# DualEncoderBoard-revd.net
KiCad netlist of a schematic drawn in EAGLE
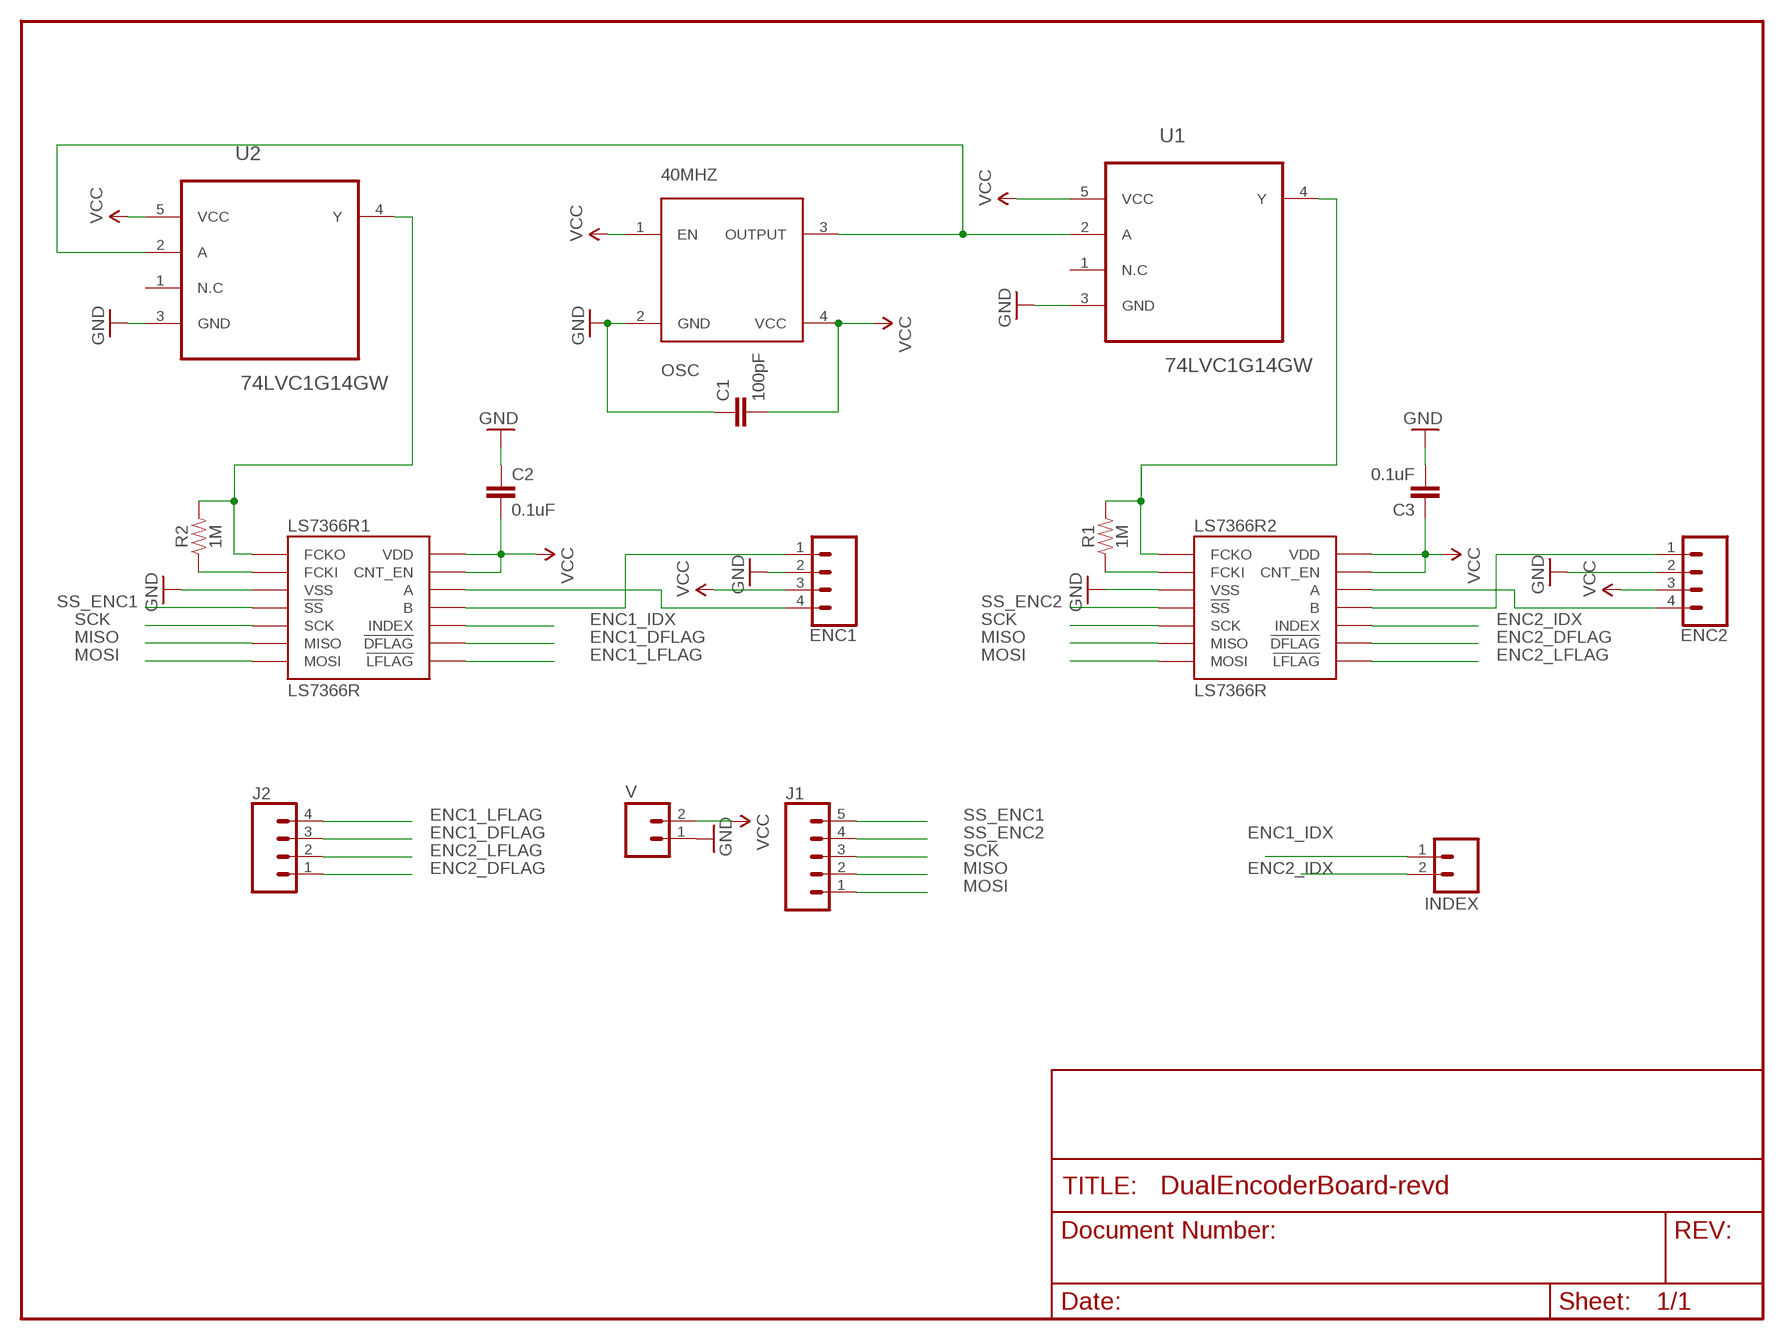
[diagram p0: schematic, sheet 1]

(export (version "E")
  (design (tool "Eeschema 10.0.6"))
  (components
    (comp (ref "40MHZ")
      (value "OSC")
      (footprint "eagle-import:CB3OSCILLATOR")
      (libsource (lib "eagle-import") (part "OSC"))
    )
    (comp (ref "C1")
      (value "100pF")
      (footprint "eagle-import:0603")
      (libsource (lib "eagle-import") (part "100PF-0603-50V-5%"))
    )
    (comp (ref "C2")
      (value "0.1uF")
      (footprint "eagle-import:0603")
      (libsource (lib "eagle-import") (part "0.1UF-0603-25V-5%"))
    )
    (comp (ref "C3")
      (value "0.1uF")
      (footprint "eagle-import:0603")
      (libsource (lib "eagle-import") (part "0.1UF-0603-25V-5%"))
    )
    (comp (ref "ENC1")
      (value "CONN_04")
      (footprint "eagle-import:1X04")
      (libsource (lib "eagle-import") (part "CONN_04"))
    )
    (comp (ref "ENC2")
      (value "CONN_04")
      (footprint "eagle-import:1X04")
      (libsource (lib "eagle-import") (part "CONN_04"))
    )
    (comp (ref "INDEX")
      (value "M02PTH")
      (footprint "eagle-import:1X02")
      (libsource (lib "eagle-import") (part "M02PTH"))
    )
    (comp (ref "J1")
      (value "CONN_05")
      (footprint "eagle-import:1X05")
      (libsource (lib "eagle-import") (part "CONN_05"))
    )
    (comp (ref "J2")
      (value "CONN_04")
      (footprint "eagle-import:1X04")
      (libsource (lib "eagle-import") (part "CONN_04"))
    )
    (comp (ref "LS7366R1")
      (value "LS7366R")
      (footprint "eagle-import:SOIC14")
      (fields (field (name "MF") "LSI"))
      (libsource (lib "eagle-import") (part "LS7366R"))
    )
    (comp (ref "LS7366R2")
      (value "LS7366R")
      (footprint "eagle-import:SOIC14")
      (fields (field (name "MF") "LSI"))
      (libsource (lib "eagle-import") (part "LS7366R"))
    )
    (comp (ref "R1")
      (value "1M")
      (footprint "eagle-import:0603")
      (libsource (lib "eagle-import") (part "1MOHM-0603-1/4W-5%"))
    )
    (comp (ref "R2")
      (value "1M")
      (footprint "eagle-import:0603")
      (libsource (lib "eagle-import") (part "1MOHM-0603-1/4W-5%"))
    )
    (comp (ref "U1")
      (value "74LVC1G14GW")
      (footprint "eagle-import:SOT65P210X110-5N")
      (fields (field (name "MF") "NXP Semiconductors"))
      (libsource (lib "eagle-import") (part "74LVC1G14GW"))
    )
    (comp (ref "U2")
      (value "74LVC1G14GW")
      (footprint "eagle-import:SOT65P210X110-5N")
      (fields (field (name "MF") "NXP Semiconductors"))
      (libsource (lib "eagle-import") (part "74LVC1G14GW"))
    )
    (comp (ref "V")
      (value "M02-JST-2MM-SMT")
      (footprint "eagle-import:JST-2-SMD")
      (libsource (lib "eagle-import") (part "M02-JST-2MM-SMT"))
    )
  )
  (nets
    (net (code "1") (name "/ENC1_DFLAG") (class "Default")
      (node (ref "J2") (pin "3") (pinfunction "3_3") (pintype "passive"))
      (node (ref "LS7366R1") (pin "9") (pinfunction "~{DFLAG}_9") (pintype "bidirectional"))
    )
    (net (code "2") (name "/ENC1_IDX") (class "Default")
      (node (ref "INDEX") (pin "1") (pinfunction "1_1") (pintype "passive"))
      (node (ref "LS7366R1") (pin "10") (pinfunction "INDEX_10") (pintype "bidirectional"))
    )
    (net (code "3") (name "/ENC1_LFLAG") (class "Default")
      (node (ref "J2") (pin "4") (pinfunction "4_4") (pintype "passive"))
      (node (ref "LS7366R1") (pin "8") (pinfunction "~{LFLAG}_8") (pintype "bidirectional"))
    )
    (net (code "4") (name "/ENC2_DFLAG") (class "Default")
      (node (ref "J2") (pin "1") (pinfunction "1_1") (pintype "passive"))
      (node (ref "LS7366R2") (pin "9") (pinfunction "~{DFLAG}_9") (pintype "bidirectional"))
    )
    (net (code "5") (name "/ENC2_IDX") (class "Default")
      (node (ref "INDEX") (pin "2") (pinfunction "2_2") (pintype "passive"))
      (node (ref "LS7366R2") (pin "10") (pinfunction "INDEX_10") (pintype "bidirectional"))
    )
    (net (code "6") (name "/ENC2_LFLAG") (class "Default")
      (node (ref "J2") (pin "2") (pinfunction "2_2") (pintype "passive"))
      (node (ref "LS7366R2") (pin "8") (pinfunction "~{LFLAG}_8") (pintype "bidirectional"))
    )
    (net (code "7") (name "/MISO") (class "Default")
      (node (ref "J1") (pin "2") (pinfunction "2_2") (pintype "passive"))
      (node (ref "LS7366R1") (pin "6") (pinfunction "MISO_6") (pintype "bidirectional"))
      (node (ref "LS7366R2") (pin "6") (pinfunction "MISO_6") (pintype "bidirectional"))
    )
    (net (code "8") (name "/MOSI") (class "Default")
      (node (ref "J1") (pin "1") (pinfunction "1_1") (pintype "passive"))
      (node (ref "LS7366R1") (pin "7") (pinfunction "MOSI_7") (pintype "bidirectional"))
      (node (ref "LS7366R2") (pin "7") (pinfunction "MOSI_7") (pintype "bidirectional"))
    )
    (net (code "9") (name "/SCK") (class "Default")
      (node (ref "J1") (pin "3") (pinfunction "3_3") (pintype "passive"))
      (node (ref "LS7366R1") (pin "5") (pinfunction "SCK_5") (pintype "bidirectional"))
      (node (ref "LS7366R2") (pin "5") (pinfunction "SCK_5") (pintype "bidirectional"))
    )
    (net (code "10") (name "/SS_ENC1") (class "Default")
      (node (ref "J1") (pin "5") (pinfunction "5_5") (pintype "passive"))
      (node (ref "LS7366R1") (pin "4") (pinfunction "~{SS}_4") (pintype "bidirectional"))
    )
    (net (code "11") (name "/SS_ENC2") (class "Default")
      (node (ref "J1") (pin "4") (pinfunction "4_4") (pintype "passive"))
      (node (ref "LS7366R2") (pin "4") (pinfunction "~{SS}_4") (pintype "bidirectional"))
    )
    (net (code "12") (name "GND") (class "Default")
      (node (ref "40MHZ") (pin "2") (pinfunction "GND_2") (pintype "input"))
      (node (ref "C1") (pin "1") (pinfunction "1_1") (pintype "passive"))
      (node (ref "C2") (pin "1") (pinfunction "1_1") (pintype "passive"))
      (node (ref "C3") (pin "2") (pinfunction "2_2") (pintype "passive"))
      (node (ref "ENC1") (pin "2") (pinfunction "2_2") (pintype "passive"))
      (node (ref "ENC2") (pin "2") (pinfunction "2_2") (pintype "passive"))
      (node (ref "LS7366R1") (pin "3") (pinfunction "VSS_3") (pintype "bidirectional"))
      (node (ref "LS7366R2") (pin "3") (pinfunction "VSS_3") (pintype "bidirectional"))
      (node (ref "U1") (pin "3") (pinfunction "GND_3") (pintype "passive"))
      (node (ref "U2") (pin "3") (pinfunction "GND_3") (pintype "passive"))
      (node (ref "V") (pin "1") (pinfunction "1_1") (pintype "passive"))
    )
    (net (code "13") (name "Net-(40MHZ-OUTPUT)") (class "Default")
      (node (ref "40MHZ") (pin "3") (pinfunction "OUTPUT_3") (pintype "output"))
      (node (ref "U1") (pin "2") (pinfunction "A_2") (pintype "input"))
      (node (ref "U2") (pin "2") (pinfunction "A_2") (pintype "input"))
    )
    (net (code "14") (name "Net-(LS7366R1-A)") (class "Default")
      (node (ref "ENC1") (pin "4") (pinfunction "4_4") (pintype "passive"))
      (node (ref "LS7366R1") (pin "12") (pinfunction "A_12") (pintype "bidirectional"))
    )
    (net (code "15") (name "Net-(LS7366R1-B)") (class "Default")
      (node (ref "ENC1") (pin "1") (pinfunction "1_1") (pintype "passive"))
      (node (ref "LS7366R1") (pin "11") (pinfunction "B_11") (pintype "bidirectional"))
    )
    (net (code "16") (name "Net-(LS7366R1-FCKI)") (class "Default")
      (node (ref "LS7366R1") (pin "2") (pinfunction "FCKI_2") (pintype "bidirectional"))
      (node (ref "R2") (pin "1") (pinfunction "1_1") (pintype "passive"))
    )
    (net (code "17") (name "Net-(LS7366R1-FCKO)") (class "Default")
      (node (ref "LS7366R1") (pin "1") (pinfunction "FCKO_1") (pintype "bidirectional"))
      (node (ref "R2") (pin "2") (pinfunction "2_2") (pintype "passive"))
      (node (ref "U2") (pin "4") (pinfunction "Y_4") (pintype "output"))
    )
    (net (code "18") (name "Net-(LS7366R2-A)") (class "Default")
      (node (ref "ENC2") (pin "4") (pinfunction "4_4") (pintype "passive"))
      (node (ref "LS7366R2") (pin "12") (pinfunction "A_12") (pintype "bidirectional"))
    )
    (net (code "19") (name "Net-(LS7366R2-B)") (class "Default")
      (node (ref "ENC2") (pin "1") (pinfunction "1_1") (pintype "passive"))
      (node (ref "LS7366R2") (pin "11") (pinfunction "B_11") (pintype "bidirectional"))
    )
    (net (code "20") (name "Net-(LS7366R2-FCKI)") (class "Default")
      (node (ref "LS7366R2") (pin "2") (pinfunction "FCKI_2") (pintype "bidirectional"))
      (node (ref "R1") (pin "1") (pinfunction "1_1") (pintype "passive"))
    )
    (net (code "21") (name "Net-(LS7366R2-FCKO)") (class "Default")
      (node (ref "LS7366R2") (pin "1") (pinfunction "FCKO_1") (pintype "bidirectional"))
      (node (ref "R1") (pin "2") (pinfunction "2_2") (pintype "passive"))
      (node (ref "U1") (pin "4") (pinfunction "Y_4") (pintype "output"))
    )
    (net (code "22") (name "VCC") (class "Default")
      (node (ref "40MHZ") (pin "1") (pinfunction "EN_1") (pintype "input"))
      (node (ref "40MHZ") (pin "4") (pinfunction "VCC_4") (pintype "input"))
      (node (ref "C1") (pin "2") (pinfunction "2_2") (pintype "passive"))
      (node (ref "C2") (pin "2") (pinfunction "2_2") (pintype "passive"))
      (node (ref "C3") (pin "1") (pinfunction "1_1") (pintype "passive"))
      (node (ref "ENC1") (pin "3") (pinfunction "3_3") (pintype "passive"))
      (node (ref "ENC2") (pin "3") (pinfunction "3_3") (pintype "passive"))
      (node (ref "LS7366R1") (pin "13") (pinfunction "CNT_EN_13") (pintype "bidirectional"))
      (node (ref "LS7366R1") (pin "14") (pinfunction "VDD_14") (pintype "bidirectional"))
      (node (ref "LS7366R2") (pin "13") (pinfunction "CNT_EN_13") (pintype "bidirectional"))
      (node (ref "LS7366R2") (pin "14") (pinfunction "VDD_14") (pintype "bidirectional"))
      (node (ref "U1") (pin "5") (pinfunction "VCC_5") (pintype "power_in"))
      (node (ref "U2") (pin "5") (pinfunction "VCC_5") (pintype "power_in"))
      (node (ref "V") (pin "2") (pinfunction "2_2") (pintype "passive"))
    )
    (net (code "23") (name "unconnected-(U1-N.C-Pad1)") (class "Default")
      (node (ref "U1") (pin "1") (pinfunction "N.C_1") (pintype "no_connect"))
    )
    (net (code "24") (name "unconnected-(U2-N.C-Pad1)") (class "Default")
      (node (ref "U2") (pin "1") (pinfunction "N.C_1") (pintype "no_connect"))
    )
  )
)
